# MPPC2.net
KiCad netlist of a schematic drawn in EAGLE
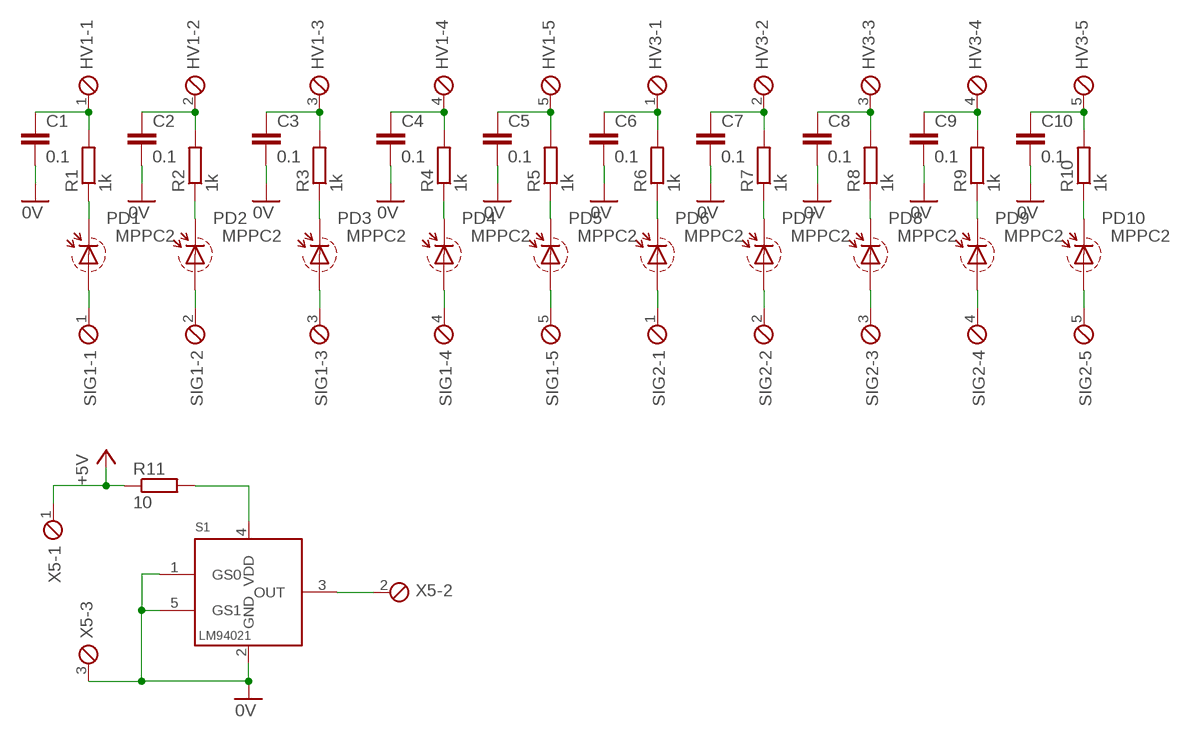
[diagram p0: schematic, sheet 1]

(export (version "E")
  (design (tool "Eeschema 10.0.6"))
  (components
    (comp (ref "C1")
      (value "0.1")
      (footprint "eagle-import:C0805K")
      (libsource (lib "eagle-import") (part "C-EUC0805K"))
    )
    (comp (ref "C2")
      (value "0.1")
      (footprint "eagle-import:C0805K")
      (libsource (lib "eagle-import") (part "C-EUC0805K"))
    )
    (comp (ref "C3")
      (value "0.1")
      (footprint "eagle-import:C0805K")
      (libsource (lib "eagle-import") (part "C-EUC0805K"))
    )
    (comp (ref "C4")
      (value "0.1")
      (footprint "eagle-import:C0805K")
      (libsource (lib "eagle-import") (part "C-EUC0805K"))
    )
    (comp (ref "C5")
      (value "0.1")
      (footprint "eagle-import:C0805K")
      (libsource (lib "eagle-import") (part "C-EUC0805K"))
    )
    (comp (ref "C6")
      (value "0.1")
      (footprint "eagle-import:C0805K")
      (libsource (lib "eagle-import") (part "C-EUC0805K"))
    )
    (comp (ref "C7")
      (value "0.1")
      (footprint "eagle-import:C0805K")
      (libsource (lib "eagle-import") (part "C-EUC0805K"))
    )
    (comp (ref "C8")
      (value "0.1")
      (footprint "eagle-import:C0805K")
      (libsource (lib "eagle-import") (part "C-EUC0805K"))
    )
    (comp (ref "C9")
      (value "0.1")
      (footprint "eagle-import:C0805K")
      (libsource (lib "eagle-import") (part "C-EUC0805K"))
    )
    (comp (ref "C10")
      (value "0.1")
      (footprint "eagle-import:C0805K")
      (libsource (lib "eagle-import") (part "C-EUC0805K"))
    )
    (comp (ref "HV1")
      (value "MPT5")
      (footprint "eagle-import:5POL254")
      (libsource (lib "eagle-import") (part "MPT5"))
    )
    (comp (ref "HV3")
      (value "MPT5")
      (footprint "eagle-import:5POL254")
      (libsource (lib "eagle-import") (part "MPT5"))
    )
    (comp (ref "PD1")
      (value "MPPC2")
      (footprint "eagle-import:S13360-6050VE")
      (libsource (lib "eagle-import") (part "MPPC2"))
    )
    (comp (ref "PD2")
      (value "MPPC2")
      (footprint "eagle-import:S13360-6050VE")
      (libsource (lib "eagle-import") (part "MPPC2"))
    )
    (comp (ref "PD3")
      (value "MPPC2")
      (footprint "eagle-import:S13360-6050VE")
      (libsource (lib "eagle-import") (part "MPPC2"))
    )
    (comp (ref "PD4")
      (value "MPPC2")
      (footprint "eagle-import:S13360-6050VE")
      (libsource (lib "eagle-import") (part "MPPC2"))
    )
    (comp (ref "PD5")
      (value "MPPC2")
      (footprint "eagle-import:S13360-6050VE")
      (libsource (lib "eagle-import") (part "MPPC2"))
    )
    (comp (ref "PD6")
      (value "MPPC2")
      (footprint "eagle-import:S13360-6050VE")
      (libsource (lib "eagle-import") (part "MPPC2"))
    )
    (comp (ref "PD7")
      (value "MPPC2")
      (footprint "eagle-import:S13360-6050VE")
      (libsource (lib "eagle-import") (part "MPPC2"))
    )
    (comp (ref "PD8")
      (value "MPPC2")
      (footprint "eagle-import:S13360-6050VE")
      (libsource (lib "eagle-import") (part "MPPC2"))
    )
    (comp (ref "PD9")
      (value "MPPC2")
      (footprint "eagle-import:S13360-6050VE")
      (libsource (lib "eagle-import") (part "MPPC2"))
    )
    (comp (ref "PD10")
      (value "MPPC2")
      (footprint "eagle-import:S13360-6050VE")
      (libsource (lib "eagle-import") (part "MPPC2"))
    )
    (comp (ref "R1")
      (value "1k")
      (footprint "eagle-import:M0805")
      (libsource (lib "eagle-import") (part "R-EU_M0805"))
    )
    (comp (ref "R2")
      (value "1k")
      (footprint "eagle-import:M0805")
      (libsource (lib "eagle-import") (part "R-EU_M0805"))
    )
    (comp (ref "R3")
      (value "1k")
      (footprint "eagle-import:M0805")
      (libsource (lib "eagle-import") (part "R-EU_M0805"))
    )
    (comp (ref "R4")
      (value "1k")
      (footprint "eagle-import:M0805")
      (libsource (lib "eagle-import") (part "R-EU_M0805"))
    )
    (comp (ref "R5")
      (value "1k")
      (footprint "eagle-import:M0805")
      (libsource (lib "eagle-import") (part "R-EU_M0805"))
    )
    (comp (ref "R6")
      (value "1k")
      (footprint "eagle-import:M0805")
      (libsource (lib "eagle-import") (part "R-EU_M0805"))
    )
    (comp (ref "R7")
      (value "1k")
      (footprint "eagle-import:M0805")
      (libsource (lib "eagle-import") (part "R-EU_M0805"))
    )
    (comp (ref "R8")
      (value "1k")
      (footprint "eagle-import:M0805")
      (libsource (lib "eagle-import") (part "R-EU_M0805"))
    )
    (comp (ref "R9")
      (value "1k")
      (footprint "eagle-import:M0805")
      (libsource (lib "eagle-import") (part "R-EU_M0805"))
    )
    (comp (ref "R10")
      (value "1k")
      (footprint "eagle-import:M0805")
      (libsource (lib "eagle-import") (part "R-EU_M0805"))
    )
    (comp (ref "R11")
      (value "10")
      (footprint "eagle-import:R0805")
      (libsource (lib "eagle-import") (part "R-EU_R0805"))
    )
    (comp (ref "S1")
      (value "LM94021")
      (footprint "eagle-import:DCK_R-PDSO-G5")
      (libsource (lib "eagle-import") (part "LM94021"))
    )
    (comp (ref "SIG1")
      (value "MPT5")
      (footprint "eagle-import:5POL254")
      (libsource (lib "eagle-import") (part "MPT5"))
    )
    (comp (ref "SIG2")
      (value "MPT5")
      (footprint "eagle-import:5POL254")
      (libsource (lib "eagle-import") (part "MPT5"))
    )
    (comp (ref "X5")
      (value "MPT3")
      (footprint "eagle-import:3POL254")
      (libsource (lib "eagle-import") (part "MPT3"))
    )
  )
  (nets
    (net (code "1") (name "+5V") (class "Default")
      (node (ref "R11") (pin "1") (pinfunction "1_1") (pintype "passive"))
      (node (ref "X5") (pin "1") (pinfunction "1_1") (pintype "passive"))
    )
    (net (code "2") (name "0V") (class "Default")
      (node (ref "C1") (pin "2") (pinfunction "2_2") (pintype "passive"))
      (node (ref "C10") (pin "2") (pinfunction "2_2") (pintype "passive"))
      (node (ref "C2") (pin "2") (pinfunction "2_2") (pintype "passive"))
      (node (ref "C3") (pin "2") (pinfunction "2_2") (pintype "passive"))
      (node (ref "C4") (pin "2") (pinfunction "2_2") (pintype "passive"))
      (node (ref "C5") (pin "2") (pinfunction "2_2") (pintype "passive"))
      (node (ref "C6") (pin "2") (pinfunction "2_2") (pintype "passive"))
      (node (ref "C7") (pin "2") (pinfunction "2_2") (pintype "passive"))
      (node (ref "C8") (pin "2") (pinfunction "2_2") (pintype "passive"))
      (node (ref "C9") (pin "2") (pinfunction "2_2") (pintype "passive"))
      (node (ref "S1") (pin "1") (pinfunction "GS0_1") (pintype "input"))
      (node (ref "S1") (pin "2") (pinfunction "GND_2") (pintype "power_in"))
      (node (ref "S1") (pin "5") (pinfunction "GS1_5") (pintype "input"))
      (node (ref "X5") (pin "3") (pinfunction "1_3") (pintype "passive"))
    )
    (net (code "3") (name "Net-(C1-Pad1)") (class "Default")
      (node (ref "C1") (pin "1") (pinfunction "1_1") (pintype "passive"))
      (node (ref "HV1") (pin "1") (pinfunction "1_1") (pintype "passive"))
      (node (ref "R1") (pin "2") (pinfunction "2_2") (pintype "passive"))
    )
    (net (code "4") (name "Net-(C6-Pad1)") (class "Default")
      (node (ref "C6") (pin "1") (pinfunction "1_1") (pintype "passive"))
      (node (ref "HV3") (pin "1") (pinfunction "1_1") (pintype "passive"))
      (node (ref "R6") (pin "2") (pinfunction "2_2") (pintype "passive"))
    )
    (net (code "5") (name "Net-(HV1B-1)") (class "Default")
      (node (ref "C2") (pin "1") (pinfunction "1_1") (pintype "passive"))
      (node (ref "HV1") (pin "2") (pinfunction "1_2") (pintype "passive"))
      (node (ref "R2") (pin "2") (pinfunction "2_2") (pintype "passive"))
    )
    (net (code "6") (name "Net-(HV1C-1)") (class "Default")
      (node (ref "C3") (pin "1") (pinfunction "1_1") (pintype "passive"))
      (node (ref "HV1") (pin "3") (pinfunction "1_3") (pintype "passive"))
      (node (ref "R3") (pin "2") (pinfunction "2_2") (pintype "passive"))
    )
    (net (code "7") (name "Net-(HV1D-1)") (class "Default")
      (node (ref "C4") (pin "1") (pinfunction "1_1") (pintype "passive"))
      (node (ref "HV1") (pin "4") (pinfunction "1_4") (pintype "passive"))
      (node (ref "R4") (pin "2") (pinfunction "2_2") (pintype "passive"))
    )
    (net (code "8") (name "Net-(HV1E-1)") (class "Default")
      (node (ref "C5") (pin "1") (pinfunction "1_1") (pintype "passive"))
      (node (ref "HV1") (pin "5") (pinfunction "1_5") (pintype "passive"))
      (node (ref "R5") (pin "2") (pinfunction "2_2") (pintype "passive"))
    )
    (net (code "9") (name "Net-(HV3B-1)") (class "Default")
      (node (ref "C7") (pin "1") (pinfunction "1_1") (pintype "passive"))
      (node (ref "HV3") (pin "2") (pinfunction "1_2") (pintype "passive"))
      (node (ref "R7") (pin "2") (pinfunction "2_2") (pintype "passive"))
    )
    (net (code "10") (name "Net-(HV3C-1)") (class "Default")
      (node (ref "C8") (pin "1") (pinfunction "1_1") (pintype "passive"))
      (node (ref "HV3") (pin "3") (pinfunction "1_3") (pintype "passive"))
      (node (ref "R8") (pin "2") (pinfunction "2_2") (pintype "passive"))
    )
    (net (code "11") (name "Net-(HV3D-1)") (class "Default")
      (node (ref "C9") (pin "1") (pinfunction "1_1") (pintype "passive"))
      (node (ref "HV3") (pin "4") (pinfunction "1_4") (pintype "passive"))
      (node (ref "R9") (pin "2") (pinfunction "2_2") (pintype "passive"))
    )
    (net (code "12") (name "Net-(HV3E-1)") (class "Default")
      (node (ref "C10") (pin "1") (pinfunction "1_1") (pintype "passive"))
      (node (ref "HV3") (pin "5") (pinfunction "1_5") (pintype "passive"))
      (node (ref "R10") (pin "2") (pinfunction "2_2") (pintype "passive"))
    )
    (net (code "13") (name "Net-(PD1-ANODE-PadA1)") (class "Default")
      (node (ref "PD1") (pin "A1") (pinfunction "ANODE_A1") (pintype "passive"))
      (node (ref "PD1") (pin "A2") (pinfunction "ANODE_A2") (pintype "passive"))
      (node (ref "PD1") (pin "A3") (pinfunction "ANODE_A3") (pintype "passive"))
      (node (ref "PD1") (pin "A4") (pinfunction "ANODE_A4") (pintype "passive"))
      (node (ref "SIG1") (pin "1") (pinfunction "1_1") (pintype "passive"))
    )
    (net (code "14") (name "Net-(PD1-CATH-PadC1)") (class "Default")
      (node (ref "PD1") (pin "C1") (pinfunction "CATH_C1") (pintype "passive"))
      (node (ref "PD1") (pin "C2") (pinfunction "CATH_C2") (pintype "passive"))
      (node (ref "PD1") (pin "C3") (pinfunction "CATH_C3") (pintype "passive"))
      (node (ref "PD1") (pin "C4") (pinfunction "CATH_C4") (pintype "passive"))
      (node (ref "R1") (pin "1") (pinfunction "1_1") (pintype "passive"))
    )
    (net (code "15") (name "Net-(PD2-CATH-PadC1)") (class "Default")
      (node (ref "PD2") (pin "C1") (pinfunction "CATH_C1") (pintype "passive"))
      (node (ref "PD2") (pin "C2") (pinfunction "CATH_C2") (pintype "passive"))
      (node (ref "PD2") (pin "C3") (pinfunction "CATH_C3") (pintype "passive"))
      (node (ref "PD2") (pin "C4") (pinfunction "CATH_C4") (pintype "passive"))
      (node (ref "R2") (pin "1") (pinfunction "1_1") (pintype "passive"))
    )
    (net (code "16") (name "Net-(PD3-CATH-PadC1)") (class "Default")
      (node (ref "PD3") (pin "C1") (pinfunction "CATH_C1") (pintype "passive"))
      (node (ref "PD3") (pin "C2") (pinfunction "CATH_C2") (pintype "passive"))
      (node (ref "PD3") (pin "C3") (pinfunction "CATH_C3") (pintype "passive"))
      (node (ref "PD3") (pin "C4") (pinfunction "CATH_C4") (pintype "passive"))
      (node (ref "R3") (pin "1") (pinfunction "1_1") (pintype "passive"))
    )
    (net (code "17") (name "Net-(PD4-CATH-PadC1)") (class "Default")
      (node (ref "PD4") (pin "C1") (pinfunction "CATH_C1") (pintype "passive"))
      (node (ref "PD4") (pin "C2") (pinfunction "CATH_C2") (pintype "passive"))
      (node (ref "PD4") (pin "C3") (pinfunction "CATH_C3") (pintype "passive"))
      (node (ref "PD4") (pin "C4") (pinfunction "CATH_C4") (pintype "passive"))
      (node (ref "R4") (pin "1") (pinfunction "1_1") (pintype "passive"))
    )
    (net (code "18") (name "Net-(PD5-CATH-PadC1)") (class "Default")
      (node (ref "PD5") (pin "C1") (pinfunction "CATH_C1") (pintype "passive"))
      (node (ref "PD5") (pin "C2") (pinfunction "CATH_C2") (pintype "passive"))
      (node (ref "PD5") (pin "C3") (pinfunction "CATH_C3") (pintype "passive"))
      (node (ref "PD5") (pin "C4") (pinfunction "CATH_C4") (pintype "passive"))
      (node (ref "R5") (pin "1") (pinfunction "1_1") (pintype "passive"))
    )
    (net (code "19") (name "Net-(PD6-ANODE-PadA1)") (class "Default")
      (node (ref "PD6") (pin "A1") (pinfunction "ANODE_A1") (pintype "passive"))
      (node (ref "PD6") (pin "A2") (pinfunction "ANODE_A2") (pintype "passive"))
      (node (ref "PD6") (pin "A3") (pinfunction "ANODE_A3") (pintype "passive"))
      (node (ref "PD6") (pin "A4") (pinfunction "ANODE_A4") (pintype "passive"))
      (node (ref "SIG2") (pin "1") (pinfunction "1_1") (pintype "passive"))
    )
    (net (code "20") (name "Net-(PD6-CATH-PadC1)") (class "Default")
      (node (ref "PD6") (pin "C1") (pinfunction "CATH_C1") (pintype "passive"))
      (node (ref "PD6") (pin "C2") (pinfunction "CATH_C2") (pintype "passive"))
      (node (ref "PD6") (pin "C3") (pinfunction "CATH_C3") (pintype "passive"))
      (node (ref "PD6") (pin "C4") (pinfunction "CATH_C4") (pintype "passive"))
      (node (ref "R6") (pin "1") (pinfunction "1_1") (pintype "passive"))
    )
    (net (code "21") (name "Net-(PD7-CATH-PadC1)") (class "Default")
      (node (ref "PD7") (pin "C1") (pinfunction "CATH_C1") (pintype "passive"))
      (node (ref "PD7") (pin "C2") (pinfunction "CATH_C2") (pintype "passive"))
      (node (ref "PD7") (pin "C3") (pinfunction "CATH_C3") (pintype "passive"))
      (node (ref "PD7") (pin "C4") (pinfunction "CATH_C4") (pintype "passive"))
      (node (ref "R7") (pin "1") (pinfunction "1_1") (pintype "passive"))
    )
    (net (code "22") (name "Net-(PD8-CATH-PadC1)") (class "Default")
      (node (ref "PD8") (pin "C1") (pinfunction "CATH_C1") (pintype "passive"))
      (node (ref "PD8") (pin "C2") (pinfunction "CATH_C2") (pintype "passive"))
      (node (ref "PD8") (pin "C3") (pinfunction "CATH_C3") (pintype "passive"))
      (node (ref "PD8") (pin "C4") (pinfunction "CATH_C4") (pintype "passive"))
      (node (ref "R8") (pin "1") (pinfunction "1_1") (pintype "passive"))
    )
    (net (code "23") (name "Net-(PD9-CATH-PadC1)") (class "Default")
      (node (ref "PD9") (pin "C1") (pinfunction "CATH_C1") (pintype "passive"))
      (node (ref "PD9") (pin "C2") (pinfunction "CATH_C2") (pintype "passive"))
      (node (ref "PD9") (pin "C3") (pinfunction "CATH_C3") (pintype "passive"))
      (node (ref "PD9") (pin "C4") (pinfunction "CATH_C4") (pintype "passive"))
      (node (ref "R9") (pin "1") (pinfunction "1_1") (pintype "passive"))
    )
    (net (code "24") (name "Net-(PD10-CATH-PadC1)") (class "Default")
      (node (ref "PD10") (pin "C1") (pinfunction "CATH_C1") (pintype "passive"))
      (node (ref "PD10") (pin "C2") (pinfunction "CATH_C2") (pintype "passive"))
      (node (ref "PD10") (pin "C3") (pinfunction "CATH_C3") (pintype "passive"))
      (node (ref "PD10") (pin "C4") (pinfunction "CATH_C4") (pintype "passive"))
      (node (ref "R10") (pin "1") (pinfunction "1_1") (pintype "passive"))
    )
    (net (code "25") (name "Net-(S1-OUT)") (class "Default")
      (node (ref "S1") (pin "3") (pinfunction "OUT_3") (pintype "output"))
      (node (ref "X5") (pin "2") (pinfunction "1_2") (pintype "passive"))
    )
    (net (code "26") (name "Net-(S1-VDD)") (class "Default")
      (node (ref "R11") (pin "2") (pinfunction "2_2") (pintype "passive"))
      (node (ref "S1") (pin "4") (pinfunction "VDD_4") (pintype "power_in"))
    )
    (net (code "27") (name "Net-(SIG1B-1)") (class "Default")
      (node (ref "PD2") (pin "A1") (pinfunction "ANODE_A1") (pintype "passive"))
      (node (ref "PD2") (pin "A2") (pinfunction "ANODE_A2") (pintype "passive"))
      (node (ref "PD2") (pin "A3") (pinfunction "ANODE_A3") (pintype "passive"))
      (node (ref "PD2") (pin "A4") (pinfunction "ANODE_A4") (pintype "passive"))
      (node (ref "SIG1") (pin "2") (pinfunction "1_2") (pintype "passive"))
    )
    (net (code "28") (name "Net-(SIG1C-1)") (class "Default")
      (node (ref "PD3") (pin "A1") (pinfunction "ANODE_A1") (pintype "passive"))
      (node (ref "PD3") (pin "A2") (pinfunction "ANODE_A2") (pintype "passive"))
      (node (ref "PD3") (pin "A3") (pinfunction "ANODE_A3") (pintype "passive"))
      (node (ref "PD3") (pin "A4") (pinfunction "ANODE_A4") (pintype "passive"))
      (node (ref "SIG1") (pin "3") (pinfunction "1_3") (pintype "passive"))
    )
    (net (code "29") (name "Net-(SIG1D-1)") (class "Default")
      (node (ref "PD4") (pin "A1") (pinfunction "ANODE_A1") (pintype "passive"))
      (node (ref "PD4") (pin "A2") (pinfunction "ANODE_A2") (pintype "passive"))
      (node (ref "PD4") (pin "A3") (pinfunction "ANODE_A3") (pintype "passive"))
      (node (ref "PD4") (pin "A4") (pinfunction "ANODE_A4") (pintype "passive"))
      (node (ref "SIG1") (pin "4") (pinfunction "1_4") (pintype "passive"))
    )
    (net (code "30") (name "Net-(SIG1E-1)") (class "Default")
      (node (ref "PD5") (pin "A1") (pinfunction "ANODE_A1") (pintype "passive"))
      (node (ref "PD5") (pin "A2") (pinfunction "ANODE_A2") (pintype "passive"))
      (node (ref "PD5") (pin "A3") (pinfunction "ANODE_A3") (pintype "passive"))
      (node (ref "PD5") (pin "A4") (pinfunction "ANODE_A4") (pintype "passive"))
      (node (ref "SIG1") (pin "5") (pinfunction "1_5") (pintype "passive"))
    )
    (net (code "31") (name "Net-(SIG2B-1)") (class "Default")
      (node (ref "PD7") (pin "A1") (pinfunction "ANODE_A1") (pintype "passive"))
      (node (ref "PD7") (pin "A2") (pinfunction "ANODE_A2") (pintype "passive"))
      (node (ref "PD7") (pin "A3") (pinfunction "ANODE_A3") (pintype "passive"))
      (node (ref "PD7") (pin "A4") (pinfunction "ANODE_A4") (pintype "passive"))
      (node (ref "SIG2") (pin "2") (pinfunction "1_2") (pintype "passive"))
    )
    (net (code "32") (name "Net-(SIG2C-1)") (class "Default")
      (node (ref "PD8") (pin "A1") (pinfunction "ANODE_A1") (pintype "passive"))
      (node (ref "PD8") (pin "A2") (pinfunction "ANODE_A2") (pintype "passive"))
      (node (ref "PD8") (pin "A3") (pinfunction "ANODE_A3") (pintype "passive"))
      (node (ref "PD8") (pin "A4") (pinfunction "ANODE_A4") (pintype "passive"))
      (node (ref "SIG2") (pin "3") (pinfunction "1_3") (pintype "passive"))
    )
    (net (code "33") (name "Net-(SIG2D-1)") (class "Default")
      (node (ref "PD9") (pin "A1") (pinfunction "ANODE_A1") (pintype "passive"))
      (node (ref "PD9") (pin "A2") (pinfunction "ANODE_A2") (pintype "passive"))
      (node (ref "PD9") (pin "A3") (pinfunction "ANODE_A3") (pintype "passive"))
      (node (ref "PD9") (pin "A4") (pinfunction "ANODE_A4") (pintype "passive"))
      (node (ref "SIG2") (pin "4") (pinfunction "1_4") (pintype "passive"))
    )
    (net (code "34") (name "Net-(SIG2E-1)") (class "Default")
      (node (ref "PD10") (pin "A1") (pinfunction "ANODE_A1") (pintype "passive"))
      (node (ref "PD10") (pin "A2") (pinfunction "ANODE_A2") (pintype "passive"))
      (node (ref "PD10") (pin "A3") (pinfunction "ANODE_A3") (pintype "passive"))
      (node (ref "PD10") (pin "A4") (pinfunction "ANODE_A4") (pintype "passive"))
      (node (ref "SIG2") (pin "5") (pinfunction "1_5") (pintype "passive"))
    )
  )
)
